# CurrentSense.net
KiCad netlist of a schematic drawn in Altium Designer
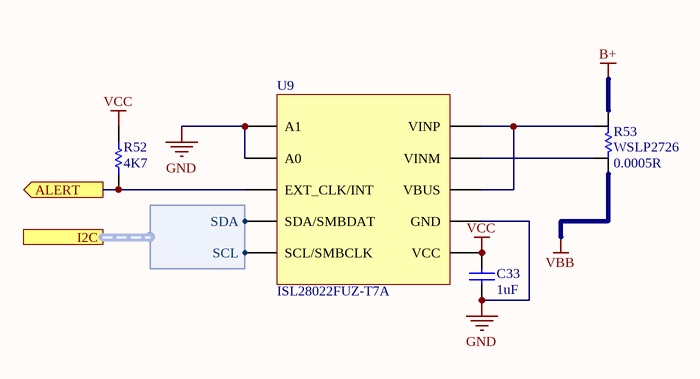
[diagram p0: CurrentSense.SchDoc]

(export (version "E")
  (design (tool "Eeschema 10.0.6"))
  (components
    (comp (ref "C33")
      (value "1uF")
      (footprint "C0603[1608X92]")
      (description "1uF 6.3V 10% 0603 (1608 Metric)")
      (fields (field (name "PARTNUMBER") "GRM188R60J105KA01D") (field (name "MANUFACTURER") "Murata"))
      (libsource (lib "Capacitors") (part "CAP_1uF_6.3V_0603_10%"))
    )
    (comp (ref "R52")
      (value "4K7")
      (footprint "R0603[1608]")
      (description "4K7 0.25W 1% 0603 (1005 Metric)")
      (fields (field (name "MANUFACTURER") "Vishay / Dale") (field (name "PARTNUMBER") "CRCW06034K70FKEAHP"))
      (libsource (lib "Resistors") (part "RES_4K7_0603_1%"))
    )
    (comp (ref "R53")
      (value "WSLP2726")
      (footprint "WSL2726")
      (description "Current Sense Resistor, 0.0005R")
      (fields
        (field (name "ALTIUM_VALUE") "0.0005R")
        (field (name "PARTNUMBER") "WSLP2726L5000FEA")
        (field (name "MANUFACTURER") "Vishay / Dale")
      )
      (libsource (lib "Components") (part "WSLP2726"))
    )
    (comp (ref "U9")
      (value "ISL28022FUZ-T7A")
      (footprint "MSOP-10")
      (fields (field (name "MANUFACTURER") "Intersil"))
      (libsource (lib "ICs") (part "ISL28022FUZ-T7A"))
    )
  )
  (nets
    (net (code "2") (name "/ALERT") (class "Default")
      (node (ref "R52") (pin "1") (pinfunction "1_1") (pintype "passive"))
      (node (ref "U9") (pin "3") (pinfunction "EXT_CLK/INT_3") (pintype "passive"))
    )
    (net (code "3") (name "/SCL") (class "Default")
      (node (ref "U9") (pin "5") (pinfunction "SCL/SMBCLK_5") (pintype "passive"))
    )
    (net (code "4") (name "/SDA") (class "Default")
      (node (ref "U9") (pin "4") (pinfunction "SDA/SMBDAT_4") (pintype "passive"))
    )
    (net (code "6") (name "B+") (class "Default")
      (node (ref "R53") (pin "2") (pinfunction "2_2") (pintype "passive"))
    )
    (net (code "7") (name "GND") (class "Default")
      (node (ref "C33") (pin "1") (pinfunction "1_1") (pintype "passive"))
      (node (ref "U9") (pin "1") (pinfunction "A1_1") (pintype "passive"))
      (node (ref "U9") (pin "2") (pinfunction "A0_2") (pintype "passive"))
      (node (ref "U9") (pin "7") (pinfunction "GND_7") (pintype "power_in"))
    )
    (net (code "8") (name "Net-(U9-VBUS)") (class "Default")
      (node (ref "R53") (pin "4") (pinfunction "4_4") (pintype "passive"))
      (node (ref "U9") (pin "10") (pinfunction "VINP_10") (pintype "passive"))
      (node (ref "U9") (pin "8") (pinfunction "VBUS_8") (pintype "passive"))
    )
    (net (code "9") (name "Net-(U9-VINM)") (class "Default")
      (node (ref "R53") (pin "3") (pinfunction "3_3") (pintype "passive"))
      (node (ref "U9") (pin "9") (pinfunction "VINM_9") (pintype "passive"))
    )
    (net (code "10") (name "VBB") (class "Default")
      (node (ref "R53") (pin "1") (pinfunction "1_1") (pintype "passive"))
    )
    (net (code "11") (name "VCC") (class "Default")
      (node (ref "C33") (pin "2") (pinfunction "2_2") (pintype "passive"))
      (node (ref "R52") (pin "2") (pinfunction "2_2") (pintype "passive"))
      (node (ref "U9") (pin "6") (pinfunction "VCC_6") (pintype "power_in"))
    )
  )
)
